# Nutaq_Adaptor.net
KiCad netlist of a schematic drawn in Altium Designer
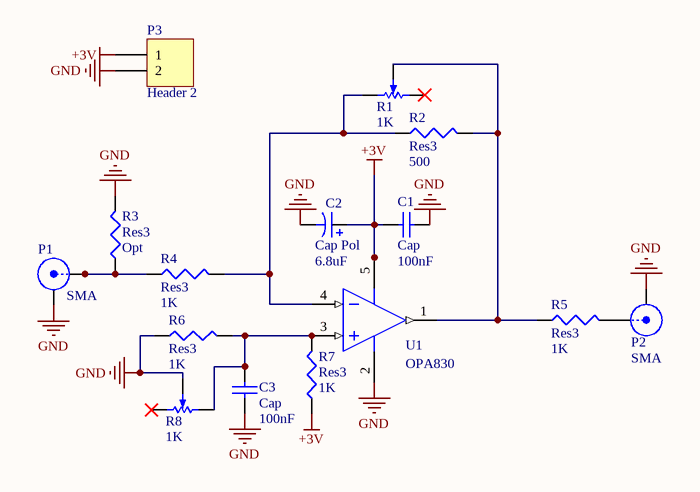
[diagram p0: Nutaq_Adaptor.SchDoc]

(export (version "E")
  (design (tool "Eeschema 10.0.6"))
  (components
    (comp (ref "C1")
      (value "Cap")
      (footprint "1608[0603]")
      (description "Capacitor (Semiconductor SIM Model)")
      (fields (field (name "ALTIUM_VALUE") "100nF") (field (name "PUBLISHER") "Altium Limited"))
      (libsource (lib "Miscellaneous Devices") (part "Cap Semi"))
    )
    (comp (ref "C2")
      (value "Cap Pol")
      (footprint "1608[0603]")
      (description "Polarized Capacitor (Surface Mount)")
      (fields (field (name "ALTIUM_VALUE") "6.8uF") (field (name "PUBLISHER") "Altium Limited"))
      (libsource (lib "Miscellaneous Devices") (part "Cap Pol3"))
    )
    (comp (ref "C3")
      (value "Cap")
      (footprint "1608[0603]")
      (description "Capacitor (Semiconductor SIM Model)")
      (fields (field (name "ALTIUM_VALUE") "100nF") (field (name "PUBLISHER") "Altium Limited"))
      (libsource (lib "Miscellaneous Devices") (part "Cap Semi"))
    )
    (comp (ref "P1")
      (value "SMA")
      (footprint "SMB_V-RJ45")
      (description "SMB Straight Connector")
      (fields (field (name "PUBLISHER") "Altium Limited"))
      (libsource (lib "Miscellaneous Connectors") (part "SMB"))
    )
    (comp (ref "P2")
      (value "SMA")
      (footprint "SMB_V-RJ45")
      (description "SMB Straight Connector")
      (fields (field (name "PUBLISHER") "Altium Limited"))
      (libsource (lib "Miscellaneous Connectors") (part "SMB"))
    )
    (comp (ref "P3")
      (value "Header 2")
      (footprint "HDR1X2")
      (description "Header, 2-Pin")
      (fields (field (name "PUBLISHER") "Altium Limited"))
      (libsource (lib "Miscellaneous Connectors") (part "Header 2"))
    )
    (comp (ref "R1")
      (value "1K")
      (footprint "POT4MM-2")
      (description "Square Trimming Potentiometer")
      (fields (field (name "PUBLISHER") "Altium Limited"))
      (libsource (lib "Miscellaneous Devices") (part "RPot SM"))
    )
    (comp (ref "R2")
      (value "Res3")
      (footprint "J1-0603")
      (description "Resistor")
      (fields (field (name "ALTIUM_VALUE") "500") (field (name "PUBLISHER") "Altium Limited"))
      (libsource (lib "Miscellaneous Devices") (part "Res3"))
    )
    (comp (ref "R3")
      (value "Res3")
      (footprint "J1-0603")
      (description "Resistor")
      (fields (field (name "ALTIUM_VALUE") "Opt") (field (name "PUBLISHER") "Altium Limited"))
      (libsource (lib "Miscellaneous Devices") (part "Res3"))
    )
    (comp (ref "R4")
      (value "Res3")
      (footprint "J1-0603")
      (description "Resistor")
      (fields (field (name "ALTIUM_VALUE") "1K") (field (name "PUBLISHER") "Altium Limited"))
      (libsource (lib "Miscellaneous Devices") (part "Res3"))
    )
    (comp (ref "R5")
      (value "Res3")
      (footprint "J1-0603")
      (description "Resistor")
      (fields (field (name "ALTIUM_VALUE") "1K") (field (name "PUBLISHER") "Altium Limited"))
      (libsource (lib "Miscellaneous Devices") (part "Res3"))
    )
    (comp (ref "R6")
      (value "Res3")
      (footprint "J1-0603")
      (description "Resistor")
      (fields (field (name "ALTIUM_VALUE") "1K") (field (name "PUBLISHER") "Altium Limited"))
      (libsource (lib "Miscellaneous Devices") (part "Res3"))
    )
    (comp (ref "R7")
      (value "Res3")
      (footprint "J1-0603")
      (description "Resistor")
      (fields (field (name "ALTIUM_VALUE") "1K") (field (name "PUBLISHER") "Altium Limited"))
      (libsource (lib "Miscellaneous Devices") (part "Res3"))
    )
    (comp (ref "R8")
      (value "1K")
      (footprint "POT4MM-2")
      (description "Square Trimming Potentiometer")
      (fields (field (name "PUBLISHER") "Altium Limited"))
      (libsource (lib "Miscellaneous Devices") (part "RPot SM"))
    )
    (comp (ref "U1")
      (value "OPA830")
      (footprint "SOT23-5_N")
      (description "300MHZ High-Speed Op Amp")
      (fields (field (name "PUBLISHER") "Altium Limited"))
      (libsource (lib "Maxim Operational Amplifier") (part "MAX477EUK-T"))
    )
  )
  (nets
    (net (code "1") (name "+3V") (class "Default")
      (node (ref "C1") (pin "1") (pinfunction "1_1") (pintype "passive"))
      (node (ref "C2") (pin "1") (pinfunction "1_1") (pintype "passive"))
      (node (ref "P3") (pin "1") (pinfunction "1_1") (pintype "passive"))
      (node (ref "R7") (pin "1") (pinfunction "1_1") (pintype "passive"))
      (node (ref "U1") (pin "5") (pinfunction "VCC_5") (pintype "power_in"))
    )
    (net (code "2") (name "GND") (class "Default")
      (node (ref "C1") (pin "2") (pinfunction "2_2") (pintype "passive"))
      (node (ref "C2") (pin "2") (pinfunction "2_2") (pintype "passive"))
      (node (ref "C3") (pin "2") (pinfunction "2_2") (pintype "passive"))
      (node (ref "P1") (pin "2") (pinfunction "Y_2") (pintype "passive"))
      (node (ref "P2") (pin "2") (pinfunction "Y_2") (pintype "passive"))
      (node (ref "P3") (pin "2") (pinfunction "2_2") (pintype "passive"))
      (node (ref "R3") (pin "2") (pinfunction "2_2") (pintype "passive"))
      (node (ref "R6") (pin "1") (pinfunction "1_1") (pintype "passive"))
      (node (ref "R8") (pin "W") (pinfunction "W_W") (pintype "passive"))
      (node (ref "U1") (pin "2") (pinfunction "VEE_2") (pintype "power_in"))
    )
    (net (code "3") (name "Net-(P1-X)") (class "Default")
      (node (ref "P1") (pin "1") (pinfunction "X_1") (pintype "passive"))
      (node (ref "R3") (pin "1") (pinfunction "1_1") (pintype "passive"))
      (node (ref "R4") (pin "1") (pinfunction "1_1") (pintype "passive"))
    )
    (net (code "4") (name "Net-(P2-X)") (class "Default")
      (node (ref "P2") (pin "1") (pinfunction "X_1") (pintype "passive"))
      (node (ref "R5") (pin "2") (pinfunction "2_2") (pintype "passive"))
    )
    (net (code "5") (name "Net-(R1-+)") (class "Default")
      (node (ref "R1") (pin "CW") (pinfunction "+_CW") (pintype "passive"))
      (node (ref "R2") (pin "1") (pinfunction "1_1") (pintype "passive"))
      (node (ref "R4") (pin "2") (pinfunction "2_2") (pintype "passive"))
      (node (ref "U1") (pin "4") (pinfunction "IN-_4") (pintype "input"))
    )
    (net (code "6") (name "Net-(R8--)") (class "Default")
      (node (ref "C3") (pin "1") (pinfunction "1_1") (pintype "passive"))
      (node (ref "R6") (pin "2") (pinfunction "2_2") (pintype "passive"))
      (node (ref "R7") (pin "2") (pinfunction "2_2") (pintype "passive"))
      (node (ref "R8") (pin "CCW") (pinfunction "-_CCW") (pintype "passive"))
      (node (ref "U1") (pin "3") (pinfunction "IN+_3") (pintype "input"))
    )
    (net (code "7") (name "Net-(U1-OUT)") (class "Default")
      (node (ref "R1") (pin "W") (pinfunction "W_W") (pintype "passive"))
      (node (ref "R2") (pin "2") (pinfunction "2_2") (pintype "passive"))
      (node (ref "R5") (pin "1") (pinfunction "1_1") (pintype "passive"))
      (node (ref "U1") (pin "1") (pinfunction "OUT_1") (pintype "output"))
    )
    (net (code "8") (name "unconnected-(R1---PadCCW)") (class "Default")
      (node (ref "R1") (pin "CCW") (pinfunction "-_CCW") (pintype "passive+no_connect"))
    )
    (net (code "9") (name "unconnected-(R8-+-PadCW)") (class "Default")
      (node (ref "R8") (pin "CW") (pinfunction "+_CW") (pintype "passive+no_connect"))
    )
  )
)
